# ConnectorBoard_no_opto.net
KiCad netlist of a schematic drawn in EAGLE
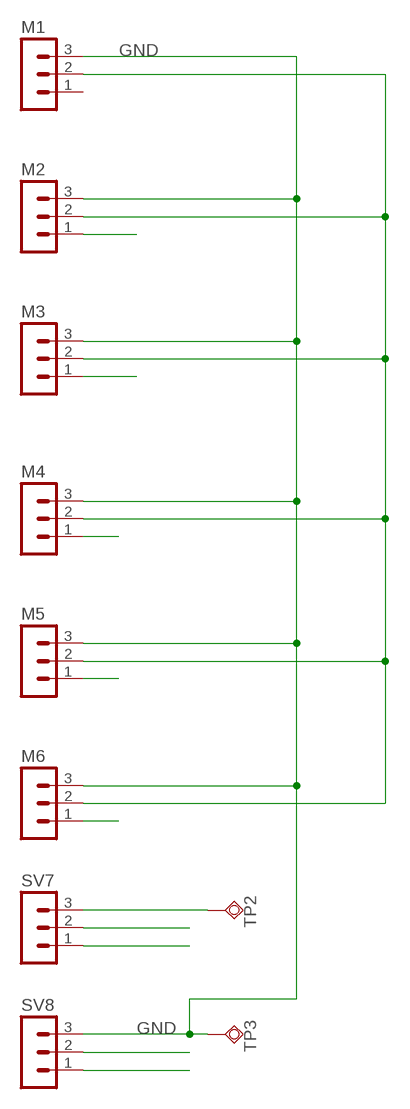
[diagram p0: schematic, sheet 1]

(export (version "E")
  (design (tool "Eeschema 10.0.6"))
  (components
    (comp (ref "M1")
      (value "MA03-1")
      (footprint "eagle-import:MA03-1")
      (libsource (lib "eagle-import") (part "MA03-1"))
    )
    (comp (ref "M2")
      (value "MA03-1")
      (footprint "eagle-import:MA03-1")
      (libsource (lib "eagle-import") (part "MA03-1"))
    )
    (comp (ref "M3")
      (value "MA03-1")
      (footprint "eagle-import:MA03-1")
      (libsource (lib "eagle-import") (part "MA03-1"))
    )
    (comp (ref "M4")
      (value "MA03-1")
      (footprint "eagle-import:MA03-1")
      (libsource (lib "eagle-import") (part "MA03-1"))
    )
    (comp (ref "M5")
      (value "MA03-1")
      (footprint "eagle-import:MA03-1")
      (libsource (lib "eagle-import") (part "MA03-1"))
    )
    (comp (ref "M6")
      (value "MA03-1")
      (footprint "eagle-import:MA03-1")
      (libsource (lib "eagle-import") (part "MA03-1"))
    )
    (comp (ref "SV7")
      (value "MA03-1")
      (footprint "eagle-import:MA03-1")
      (libsource (lib "eagle-import") (part "MA03-1"))
    )
    (comp (ref "SV8")
      (value "MA03-1")
      (footprint "eagle-import:MA03-1")
      (libsource (lib "eagle-import") (part "MA03-1"))
    )
    (comp (ref "TP2")
      (value "TPSQTP14SQ")
      (footprint "eagle-import:TP14SQ")
      (libsource (lib "eagle-import") (part "TPSQTP14SQ"))
    )
    (comp (ref "TP3")
      (value "TPSQTP14SQ")
      (footprint "eagle-import:TP14SQ")
      (libsource (lib "eagle-import") (part "TPSQTP14SQ"))
    )
  )
  (nets
    (net (code "1") (name "/GND") (class "Default")
      (node (ref "M1") (pin "3") (pinfunction "3_3") (pintype "passive"))
      (node (ref "M2") (pin "3") (pinfunction "3_3") (pintype "passive"))
      (node (ref "M3") (pin "3") (pinfunction "3_3") (pintype "passive"))
      (node (ref "M4") (pin "3") (pinfunction "3_3") (pintype "passive"))
      (node (ref "M5") (pin "3") (pinfunction "3_3") (pintype "passive"))
      (node (ref "M6") (pin "3") (pinfunction "3_3") (pintype "passive"))
      (node (ref "SV8") (pin "3") (pinfunction "3_3") (pintype "passive"))
      (node (ref "TP3") (pin "TP") (pinfunction "TP_TP") (pintype "input"))
    )
    (net (code "2") (name "Net-(M1-Pad2)") (class "Default")
      (node (ref "M1") (pin "2") (pinfunction "2_2") (pintype "passive"))
      (node (ref "M2") (pin "2") (pinfunction "2_2") (pintype "passive"))
      (node (ref "M3") (pin "2") (pinfunction "2_2") (pintype "passive"))
      (node (ref "M4") (pin "2") (pinfunction "2_2") (pintype "passive"))
      (node (ref "M5") (pin "2") (pinfunction "2_2") (pintype "passive"))
      (node (ref "M6") (pin "2") (pinfunction "2_2") (pintype "passive"))
    )
    (net (code "3") (name "Net-(SV7-Pad3)") (class "Default")
      (node (ref "SV7") (pin "3") (pinfunction "3_3") (pintype "passive"))
      (node (ref "TP2") (pin "TP") (pinfunction "TP_TP") (pintype "input"))
    )
    (net (code "4") (name "unconnected-(M1-Pad1)") (class "Default")
      (node (ref "M1") (pin "1") (pinfunction "1_1") (pintype "passive"))
    )
    (net (code "5") (name "unconnected-(M2-Pad1)") (class "Default")
      (node (ref "M2") (pin "1") (pinfunction "1_1") (pintype "passive"))
    )
    (net (code "6") (name "unconnected-(M3-Pad1)") (class "Default")
      (node (ref "M3") (pin "1") (pinfunction "1_1") (pintype "passive"))
    )
    (net (code "7") (name "unconnected-(M4-Pad1)") (class "Default")
      (node (ref "M4") (pin "1") (pinfunction "1_1") (pintype "passive"))
    )
    (net (code "8") (name "unconnected-(M5-Pad1)") (class "Default")
      (node (ref "M5") (pin "1") (pinfunction "1_1") (pintype "passive"))
    )
    (net (code "9") (name "unconnected-(M6-Pad1)") (class "Default")
      (node (ref "M6") (pin "1") (pinfunction "1_1") (pintype "passive"))
    )
    (net (code "10") (name "unconnected-(SV7-Pad1)") (class "Default")
      (node (ref "SV7") (pin "1") (pinfunction "1_1") (pintype "passive"))
    )
    (net (code "11") (name "unconnected-(SV7-Pad2)") (class "Default")
      (node (ref "SV7") (pin "2") (pinfunction "2_2") (pintype "passive"))
    )
    (net (code "12") (name "unconnected-(SV8-Pad1)") (class "Default")
      (node (ref "SV8") (pin "1") (pinfunction "1_1") (pintype "passive"))
    )
    (net (code "13") (name "unconnected-(SV8-Pad2)") (class "Default")
      (node (ref "SV8") (pin "2") (pinfunction "2_2") (pintype "passive"))
    )
  )
)
